# 04_SENSOR_SHT30_PIR_TSL2561.net
KiCad netlist of a schematic drawn in Altium Designer
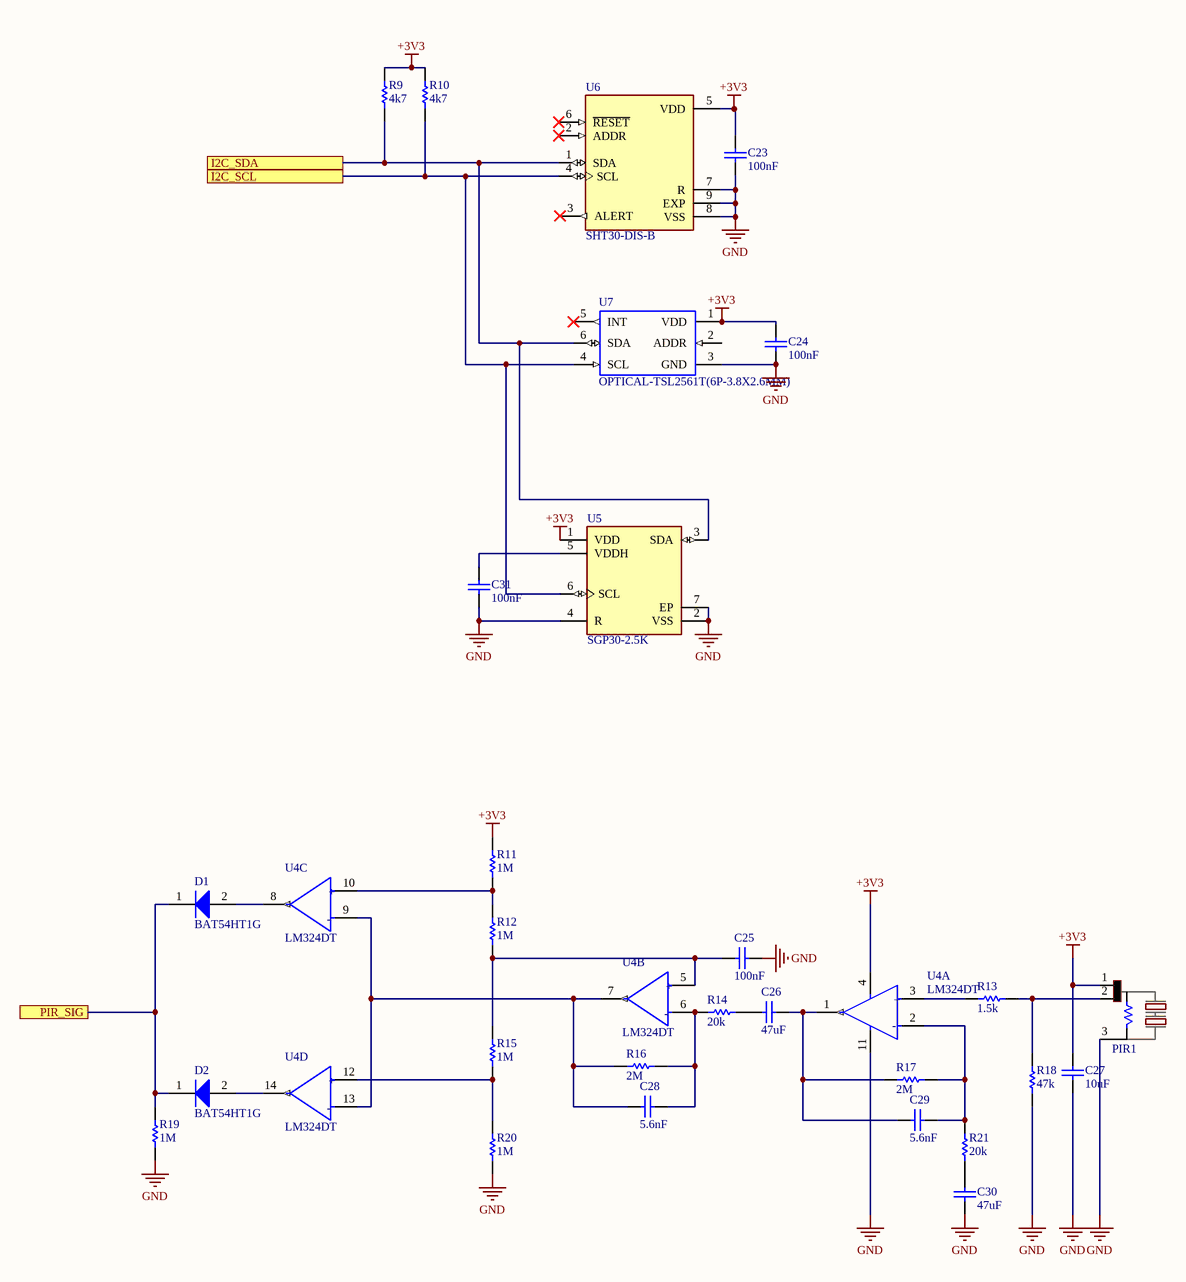
[diagram p0: 04. SENSOR SHT30, PIR, TSL2561.SchDoc]

(export (version "E")
  (design (tool "Eeschema 10.0.6"))
  (components
    (comp (ref "C23")
      (value "100nF")
      (footprint "CAPC1005X56X25NL10T15")
      (fields
        (field (name "MANUFACTURER") "AVX Interconnect / Elco")
        (field (name "PART NUMBER") "04026D104KAT2A")
      )
      (libsource (lib "Altium Content Vault") (part "CAP"))
    )
    (comp (ref "C24")
      (value "100nF")
      (footprint "CAPC1005X56X25NL10T15")
      (fields
        (field (name "MANUFACTURER") "AVX Interconnect / Elco")
        (field (name "PART NUMBER") "04026D104KAT2A")
      )
      (libsource (lib "Altium Content Vault") (part "CAP"))
    )
    (comp (ref "C25")
      (value "100nF")
      (footprint "CAPC1005X56X25NL10T15")
      (fields
        (field (name "MANUFACTURER") "AVX Interconnect / Elco")
        (field (name "PART NUMBER") "04026D104KAT2A")
      )
      (libsource (lib "Altium Content Vault") (part "CAP"))
    )
    (comp (ref "C26")
      (value "47uF")
      (footprint "CAPC1608X90X35NL10T15")
      (fields (field (name "PART NUMBER") "GRM188R60J106ME47D") (field (name "MANUFACTURER") "Murata"))
      (libsource (lib "Altium Content Vault") (part "CAP"))
    )
    (comp (ref "C27")
      (value "10uF")
      (footprint "CAPC1608X90X35NL10T15")
      (fields (field (name "PART NUMBER") "GRM188R60J106ME47D") (field (name "MANUFACTURER") "Murata"))
      (libsource (lib "Altium Content Vault") (part "CAP"))
    )
    (comp (ref "C28")
      (value "5.6nF")
      (footprint "CAPC1005X56X25NL10T15")
      (fields
        (field (name "MANUFACTURER") "AVX Interconnect / Elco")
        (field (name "PART NUMBER") "04026D104KAT2A")
      )
      (libsource (lib "Altium Content Vault") (part "CAP"))
    )
    (comp (ref "C29")
      (value "5.6nF")
      (footprint "CAPC1005X56X25NL10T15")
      (fields
        (field (name "MANUFACTURER") "AVX Interconnect / Elco")
        (field (name "PART NUMBER") "04026D104KAT2A")
      )
      (libsource (lib "Altium Content Vault") (part "CAP"))
    )
    (comp (ref "C30")
      (value "47uF")
      (footprint "CAPC1608X90X35NL10T15")
      (fields (field (name "PART NUMBER") "GRM188R60J106ME47D") (field (name "MANUFACTURER") "Murata"))
      (libsource (lib "Altium Content Vault") (part "CAP"))
    )
    (comp (ref "C31")
      (value "100nF")
      (footprint "CAPC1005X56X25NL10T15")
      (fields
        (field (name "MANUFACTURER") "AVX Interconnect / Elco")
        (field (name "PART NUMBER") "04026D104KAT2A")
      )
      (libsource (lib "Altium Content Vault") (part "CAP"))
    )
    (comp (ref "D1")
      (value "BAT54HT1G")
      (footprint "ONSC-SOD-323-2-477-02_V")
      (description "Schottky Barrier Diode, 2-Pin SOD-323, Pb-Free, Tape and Reel")
      (fields (field (name "MANUFACTURER") "On Semiconductor"))
      (libsource (lib "Altium Content Vault") (part "ONSC-D-K1A2-2"))
    )
    (comp (ref "D2")
      (value "BAT54HT1G")
      (footprint "ONSC-SOD-323-2-477-02_V")
      (description "Schottky Barrier Diode, 2-Pin SOD-323, Pb-Free, Tape and Reel")
      (fields (field (name "MANUFACTURER") "On Semiconductor"))
      (libsource (lib "Altium Content Vault") (part "ONSC-D-K1A2-2"))
    )
    (comp (ref "PIR1")
      (value "D203S")
      (footprint "D203B PIR")
      (libsource (lib "SyTungNguyen") (part "D203S"))
    )
    (comp (ref "R9")
      (value "4k7")
      (footprint "RESC1005X40X25NL05T05")
      (description "Chip Resistor, 10 KOhm, +/- 1%, 0.1 W, -55 to 155 degC, 0402 (1005 Metric), RoHS, Tape and Reel")
      (fields (field (name "TOLERANCE") "1%") (field (name "MANUFACTURER") "Panasonic"))
      (libsource (lib "Altium Content Vault") (part "RES-2"))
    )
    (comp (ref "R10")
      (value "4k7")
      (footprint "RESC1005X40X25NL05T05")
      (description "Chip Resistor, 10 KOhm, +/- 1%, 0.1 W, -55 to 155 degC, 0402 (1005 Metric), RoHS, Tape and Reel")
      (fields (field (name "TOLERANCE") "1%") (field (name "MANUFACTURER") "Panasonic"))
      (libsource (lib "Altium Content Vault") (part "RES-2"))
    )
    (comp (ref "R11")
      (value "1M")
      (footprint "RESC1005X40X25NL05T05")
      (description "Chip Resistor, 10 KOhm, +/- 1%, 0.1 W, -55 to 155 degC, 0402 (1005 Metric), RoHS, Tape and Reel")
      (fields (field (name "TOLERANCE") "1%") (field (name "MANUFACTURER") "Panasonic"))
      (libsource (lib "Altium Content Vault") (part "RES-2"))
    )
    (comp (ref "R12")
      (value "1M")
      (footprint "RESC1005X40X25NL05T05")
      (description "Chip Resistor, 10 KOhm, +/- 1%, 0.1 W, -55 to 155 degC, 0402 (1005 Metric), RoHS, Tape and Reel")
      (fields (field (name "TOLERANCE") "1%") (field (name "MANUFACTURER") "Panasonic"))
      (libsource (lib "Altium Content Vault") (part "RES-2"))
    )
    (comp (ref "R13")
      (value "1.5k")
      (footprint "RESC1005X40X25NL05T05")
      (description "Chip Resistor, 10 KOhm, +/- 1%, 0.1 W, -55 to 155 degC, 0402 (1005 Metric), RoHS, Tape and Reel")
      (fields (field (name "TOLERANCE") "1%") (field (name "MANUFACTURER") "Panasonic"))
      (libsource (lib "Altium Content Vault") (part "RES-2"))
    )
    (comp (ref "R14")
      (value "20k")
      (footprint "RESC1005X40X25NL05T05")
      (description "Chip Resistor, 10 KOhm, +/- 1%, 0.1 W, -55 to 155 degC, 0402 (1005 Metric), RoHS, Tape and Reel")
      (fields (field (name "TOLERANCE") "1%") (field (name "MANUFACTURER") "Panasonic"))
      (libsource (lib "Altium Content Vault") (part "RES-2"))
    )
    (comp (ref "R15")
      (value "1M")
      (footprint "RESC1005X40X25NL05T05")
      (description "Chip Resistor, 10 KOhm, +/- 1%, 0.1 W, -55 to 155 degC, 0402 (1005 Metric), RoHS, Tape and Reel")
      (fields (field (name "TOLERANCE") "1%") (field (name "MANUFACTURER") "Panasonic"))
      (libsource (lib "Altium Content Vault") (part "RES-2"))
    )
    (comp (ref "R16")
      (value "2M")
      (footprint "RESC1005X40X25NL05T05")
      (description "Chip Resistor, 10 KOhm, +/- 1%, 0.1 W, -55 to 155 degC, 0402 (1005 Metric), RoHS, Tape and Reel")
      (fields (field (name "TOLERANCE") "1%") (field (name "MANUFACTURER") "Panasonic"))
      (libsource (lib "Altium Content Vault") (part "RES-2"))
    )
    (comp (ref "R17")
      (value "2M")
      (footprint "RESC1005X40X25NL05T05")
      (description "Chip Resistor, 10 KOhm, +/- 1%, 0.1 W, -55 to 155 degC, 0402 (1005 Metric), RoHS, Tape and Reel")
      (fields (field (name "TOLERANCE") "1%") (field (name "MANUFACTURER") "Panasonic"))
      (libsource (lib "Altium Content Vault") (part "RES-2"))
    )
    (comp (ref "R18")
      (value "47k")
      (footprint "RESC1005X40X25NL05T05")
      (description "Chip Resistor, 10 KOhm, +/- 1%, 0.1 W, -55 to 155 degC, 0402 (1005 Metric), RoHS, Tape and Reel")
      (fields (field (name "TOLERANCE") "1%") (field (name "MANUFACTURER") "Panasonic"))
      (libsource (lib "Altium Content Vault") (part "RES-2"))
    )
    (comp (ref "R19")
      (value "1M")
      (footprint "RESC1005X40X25NL05T05")
      (description "Chip Resistor, 10 KOhm, +/- 1%, 0.1 W, -55 to 155 degC, 0402 (1005 Metric), RoHS, Tape and Reel")
      (fields (field (name "TOLERANCE") "1%") (field (name "MANUFACTURER") "Panasonic"))
      (libsource (lib "Altium Content Vault") (part "RES-2"))
    )
    (comp (ref "R20")
      (value "1M")
      (footprint "RESC1005X40X25NL05T05")
      (description "Chip Resistor, 10 KOhm, +/- 1%, 0.1 W, -55 to 155 degC, 0402 (1005 Metric), RoHS, Tape and Reel")
      (fields (field (name "TOLERANCE") "1%") (field (name "MANUFACTURER") "Panasonic"))
      (libsource (lib "Altium Content Vault") (part "RES-2"))
    )
    (comp (ref "R21")
      (value "20k")
      (footprint "RESC1005X40X25NL05T05")
      (description "Chip Resistor, 10 KOhm, +/- 1%, 0.1 W, -55 to 155 degC, 0402 (1005 Metric), RoHS, Tape and Reel")
      (fields (field (name "TOLERANCE") "1%") (field (name "MANUFACTURER") "Panasonic"))
      (libsource (lib "Altium Content Vault") (part "RES-2"))
    )
    (comp (ref "U4")
      (value "LM324DT")
      (footprint "FP-SO-14-MFG")
      (description "IC OPAMP GP 4 CIRCUIT 14SO")
      (fields
        (field (name "OCTOPART") "https://octopart.com/lm324dt-stmicroelectronics-39579146")
        (field (name "MANUFACTURER") "STMicroelectronics")
      )
      (libsource (lib "Altium Content Vault") (part "a065ef67e5aa9ef3942d43d6008d043"))
    )
    (comp (ref "U5")
      (value "SGP30-2.5K")
      (footprint "FP-SGP30-2_5K-MFG")
      (description "AIR QUALITY GAS SENSOR FOR VOC'S")
      (fields
        (field (name "OCTOPART") "https://octopart.com/sgp30-2.5k-sensirion-84561789")
        (field (name "MANUFACTURER") "Sensirion")
      )
      (libsource (lib "Altium Content Vault") (part "83c16ec1942eefe8a5a6f6958230d5f"))
    )
    (comp (ref "U6")
      (value "SHT30-DIS-B")
      (footprint "DFN250X250X100-9N")
      (description "Humidity Temperature Sensor 0 ~ 100% RH IÂ²C Â±3% RH 8s Surface Mount")
      (fields (field (name "MF") "Sensirion AG"))
      (libsource (lib "SyTungNguyen") (part "SHT30-DIS-B"))
    )
    (comp (ref "U7")
      (value "OPTICAL-TSL2561T(6P-3.8X2.6MM)")
      (footprint "TMB6-1.55-3.8X2.6MM")
      (description "Optical Sensor Ambient 640nm IÂ²C 6-SMD, No Lead")
      (fields (field (name "MP") "TSL2561T") (field (name "MF") "ams"))
      (libsource (lib "SyTungNguyen") (part "OPTICAL-TSL2561T(6P-3.8X2.6MM)"))
    )
  )
  (nets
    (net (code "1") (name "+3V3") (class "Default")
      (node (ref "C23") (pin "2") (pinfunction "2_2") (pintype "passive"))
      (node (ref "C24") (pin "2") (pinfunction "2_2") (pintype "passive"))
      (node (ref "C27") (pin "1") (pinfunction "1_1") (pintype "passive"))
      (node (ref "PIR1") (pin "1") (pinfunction "VDD_1") (pintype "passive"))
      (node (ref "R10") (pin "2") (pinfunction "2_2") (pintype "passive"))
      (node (ref "R11") (pin "2") (pinfunction "2_2") (pintype "passive"))
      (node (ref "R9") (pin "2") (pinfunction "2_2") (pintype "passive"))
      (node (ref "U4") (pin "4") (pinfunction "VCC+_4") (pintype "power_in"))
      (node (ref "U5") (pin "1") (pinfunction "VDD_1") (pintype "power_in"))
      (node (ref "U6") (pin "5") (pinfunction "VDD_5") (pintype "power_in"))
      (node (ref "U7") (pin "1") (pinfunction "VDD_1") (pintype "power_in"))
    )
    (net (code "2") (name "/I2C_SCL") (class "Default")
      (node (ref "R10") (pin "1") (pinfunction "1_1") (pintype "passive"))
      (node (ref "U5") (pin "6") (pinfunction "SCL_6") (pintype "bidirectional"))
      (node (ref "U6") (pin "4") (pinfunction "SCL_4") (pintype "bidirectional"))
      (node (ref "U7") (pin "4") (pinfunction "SCL_4") (pintype "input"))
    )
    (net (code "3") (name "/I2C_SDA") (class "Default")
      (node (ref "R9") (pin "1") (pinfunction "1_1") (pintype "passive"))
      (node (ref "U5") (pin "3") (pinfunction "SDA_3") (pintype "bidirectional"))
      (node (ref "U6") (pin "1") (pinfunction "SDA_1") (pintype "bidirectional"))
      (node (ref "U7") (pin "6") (pinfunction "SDA_6") (pintype "bidirectional"))
    )
    (net (code "4") (name "/PIR_SIG") (class "Default")
      (node (ref "D1") (pin "1") (pinfunction "K_1") (pintype "passive"))
      (node (ref "D2") (pin "1") (pinfunction "K_1") (pintype "passive"))
      (node (ref "R19") (pin "2") (pinfunction "2_2") (pintype "passive"))
    )
    (net (code "5") (name "GND") (class "Default")
      (node (ref "C23") (pin "1") (pinfunction "1_1") (pintype "passive"))
      (node (ref "C24") (pin "1") (pinfunction "1_1") (pintype "passive"))
      (node (ref "C25") (pin "2") (pinfunction "2_2") (pintype "passive"))
      (node (ref "C27") (pin "2") (pinfunction "2_2") (pintype "passive"))
      (node (ref "C30") (pin "1") (pinfunction "1_1") (pintype "passive"))
      (node (ref "C31") (pin "1") (pinfunction "1_1") (pintype "passive"))
      (node (ref "PIR1") (pin "3") (pinfunction "VDD_3") (pintype "passive"))
      (node (ref "R18") (pin "2") (pinfunction "2_2") (pintype "passive"))
      (node (ref "R19") (pin "1") (pinfunction "1_1") (pintype "passive"))
      (node (ref "R20") (pin "1") (pinfunction "1_1") (pintype "passive"))
      (node (ref "U4") (pin "11") (pinfunction "VCC-_11") (pintype "power_in"))
      (node (ref "U5") (pin "2") (pinfunction "VSS_2") (pintype "power_in"))
      (node (ref "U5") (pin "4") (pinfunction "R_4") (pintype "power_in"))
      (node (ref "U5") (pin "7") (pinfunction "EP_7") (pintype "passive"))
      (node (ref "U6") (pin "7") (pinfunction "R_7") (pintype "passive"))
      (node (ref "U6") (pin "8") (pinfunction "VSS_8") (pintype "passive"))
      (node (ref "U6") (pin "9") (pinfunction "EXP_9") (pintype "passive"))
      (node (ref "U7") (pin "3") (pinfunction "GND_3") (pintype "power_in"))
    )
    (net (code "6") (name "Net-(C26-Pad1)") (class "Default")
      (node (ref "C26") (pin "1") (pinfunction "1_1") (pintype "passive"))
      (node (ref "R14") (pin "1") (pinfunction "1_1") (pintype "passive"))
    )
    (net (code "7") (name "Net-(C30-Pad2)") (class "Default")
      (node (ref "C30") (pin "2") (pinfunction "2_2") (pintype "passive"))
      (node (ref "R21") (pin "2") (pinfunction "2_2") (pintype "passive"))
    )
    (net (code "8") (name "Net-(D1-A)") (class "Default")
      (node (ref "D1") (pin "2") (pinfunction "A_2") (pintype "passive"))
      (node (ref "U4") (pin "8") (pinfunction "Output_3_8") (pintype "output"))
    )
    (net (code "9") (name "Net-(D2-A)") (class "Default")
      (node (ref "D2") (pin "2") (pinfunction "A_2") (pintype "passive"))
      (node (ref "U4") (pin "14") (pinfunction "Output_4_14") (pintype "output"))
    )
    (net (code "10") (name "Net-(PIR1-G)") (class "Default")
      (node (ref "PIR1") (pin "2") (pinfunction "G_2") (pintype "passive"))
      (node (ref "R13") (pin "2") (pinfunction "2_2") (pintype "passive"))
      (node (ref "R18") (pin "1") (pinfunction "1_1") (pintype "passive"))
    )
    (net (code "11") (name "Net-(U4A-Inverting_Input_1)") (class "Default")
      (node (ref "C29") (pin "2") (pinfunction "2_2") (pintype "passive"))
      (node (ref "R17") (pin "1") (pinfunction "1_1") (pintype "passive"))
      (node (ref "R21") (pin "1") (pinfunction "1_1") (pintype "passive"))
      (node (ref "U4") (pin "2") (pinfunction "Inverting_Input_1_2") (pintype "tri_state"))
    )
    (net (code "12") (name "Net-(U4A-Non-Inverting_Input_1)") (class "Default")
      (node (ref "R13") (pin "1") (pinfunction "1_1") (pintype "passive"))
      (node (ref "U4") (pin "3") (pinfunction "Non-Inverting_Input_1_3") (pintype "tri_state"))
    )
    (net (code "13") (name "Net-(U4A-Output_1)") (class "Default")
      (node (ref "C26") (pin "2") (pinfunction "2_2") (pintype "passive"))
      (node (ref "C29") (pin "1") (pinfunction "1_1") (pintype "passive"))
      (node (ref "R17") (pin "2") (pinfunction "2_2") (pintype "passive"))
      (node (ref "U4") (pin "1") (pinfunction "Output_1_1") (pintype "output"))
    )
    (net (code "14") (name "Net-(U4B-Inverting_Input_2)") (class "Default")
      (node (ref "C28") (pin "2") (pinfunction "2_2") (pintype "passive"))
      (node (ref "R14") (pin "2") (pinfunction "2_2") (pintype "passive"))
      (node (ref "R16") (pin "1") (pinfunction "1_1") (pintype "passive"))
      (node (ref "U4") (pin "6") (pinfunction "Inverting_Input_2_6") (pintype "tri_state"))
    )
    (net (code "15") (name "Net-(U4B-Non-Inverting_Input_2)") (class "Default")
      (node (ref "C25") (pin "1") (pinfunction "1_1") (pintype "passive"))
      (node (ref "R12") (pin "1") (pinfunction "1_1") (pintype "passive"))
      (node (ref "R15") (pin "2") (pinfunction "2_2") (pintype "passive"))
      (node (ref "U4") (pin "5") (pinfunction "Non-Inverting_Input_2_5") (pintype "tri_state"))
    )
    (net (code "16") (name "Net-(U4B-Output_2)") (class "Default")
      (node (ref "C28") (pin "1") (pinfunction "1_1") (pintype "passive"))
      (node (ref "R16") (pin "2") (pinfunction "2_2") (pintype "passive"))
      (node (ref "U4") (pin "13") (pinfunction "Inverting_Input_4_13") (pintype "tri_state"))
      (node (ref "U4") (pin "7") (pinfunction "Output_2_7") (pintype "output"))
      (node (ref "U4") (pin "9") (pinfunction "Inverting_Input_3_9") (pintype "tri_state"))
    )
    (net (code "17") (name "Net-(U4C-Non-Inverting_Input_3)") (class "Default")
      (node (ref "R11") (pin "1") (pinfunction "1_1") (pintype "passive"))
      (node (ref "R12") (pin "2") (pinfunction "2_2") (pintype "passive"))
      (node (ref "U4") (pin "10") (pinfunction "Non-Inverting_Input_3_10") (pintype "tri_state"))
    )
    (net (code "18") (name "Net-(U4D-Non-Inverting_Input_4)") (class "Default")
      (node (ref "R15") (pin "1") (pinfunction "1_1") (pintype "passive"))
      (node (ref "R20") (pin "2") (pinfunction "2_2") (pintype "passive"))
      (node (ref "U4") (pin "12") (pinfunction "Non-Inverting_Input_4_12") (pintype "tri_state"))
    )
    (net (code "19") (name "Net-(U5-VDDH)") (class "Default")
      (node (ref "C31") (pin "2") (pinfunction "2_2") (pintype "passive"))
      (node (ref "U5") (pin "5") (pinfunction "VDDH_5") (pintype "power_in"))
    )
    (net (code "20") (name "unconnected-(U6-ADDR-Pad2)") (class "Default")
      (node (ref "U6") (pin "2") (pinfunction "ADDR_2") (pintype "input+no_connect"))
    )
    (net (code "21") (name "unconnected-(U6-ALERT-Pad3)") (class "Default")
      (node (ref "U6") (pin "3") (pinfunction "ALERT_3") (pintype "output+no_connect"))
    )
    (net (code "22") (name "unconnected-(U6-~{RESET}-Pad6)") (class "Default")
      (node (ref "U6") (pin "6") (pinfunction "~{RESET}_6") (pintype "input+no_connect"))
    )
    (net (code "23") (name "unconnected-(U7-ADDR-Pad2)") (class "Default")
      (node (ref "U7") (pin "2") (pinfunction "ADDR_2") (pintype "input"))
    )
    (net (code "24") (name "unconnected-(U7-INT-Pad5)") (class "Default")
      (node (ref "U7") (pin "5") (pinfunction "INT_5") (pintype "output+no_connect"))
    )
  )
)
